# Microcontroller.net
KiCad netlist of a schematic drawn in Altium Designer
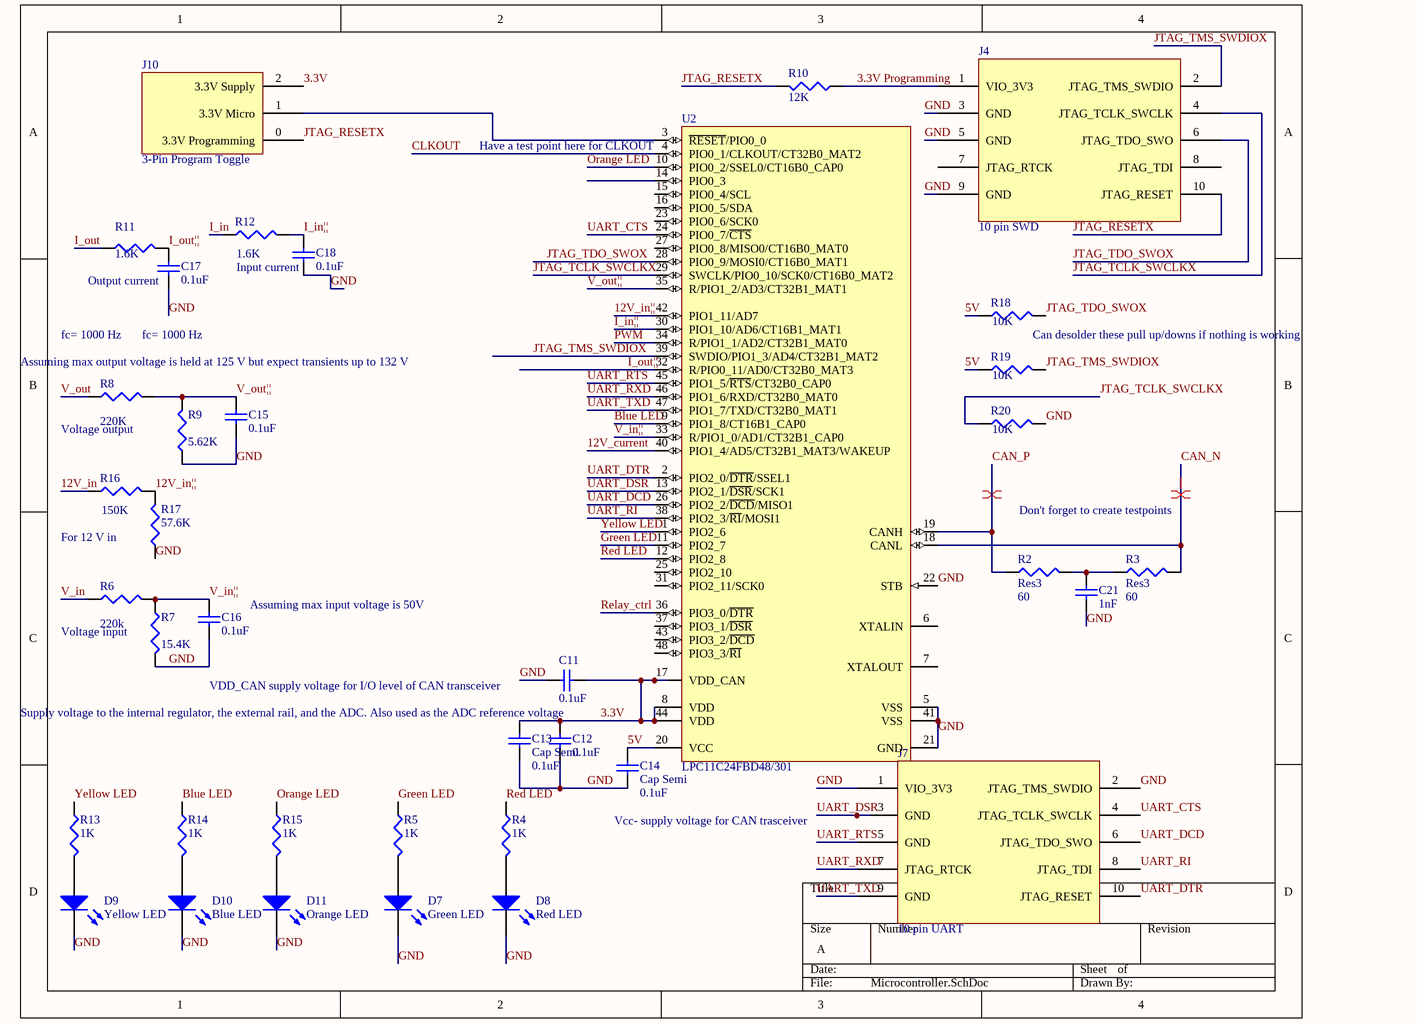
[diagram p0: Microcontroller.SchDoc]

(export (version "E")
  (design (tool "Eeschema 10.0.6"))
  (components
    (comp (ref "C11")
      (value "0.1uF")
      (footprint "C1206")
      (description "Capacitor (Semiconductor SIM Model)")
      (fields (field (name "Comment") "Cap Semi") (field (name "PUBLISHER") "Altium Limited"))
      (libsource (lib "Miscellaneous Devices") (part "Cap Semi"))
    )
    (comp (ref "C12")
      (value "0.1uF")
      (footprint "C1206")
      (description "Capacitor (Semiconductor SIM Model)")
      (fields (field (name "Comment") "Cap Semi") (field (name "PUBLISHER") "Altium Limited"))
      (libsource (lib "Miscellaneous Devices") (part "Cap Semi"))
    )
    (comp (ref "C13")
      (value "Cap Semi")
      (footprint "C1206")
      (description "Capacitor (Semiconductor SIM Model)")
      (fields (field (name "ALTIUM_VALUE") "0.1uF") (field (name "PUBLISHER") "Altium Limited"))
      (libsource (lib "Miscellaneous Devices") (part "Cap Semi"))
    )
    (comp (ref "C14")
      (value "Cap Semi")
      (footprint "C1206")
      (description "Capacitor (Semiconductor SIM Model)")
      (fields (field (name "ALTIUM_VALUE") "0.1uF") (field (name "PUBLISHER") "Altium Limited"))
      (libsource (lib "Miscellaneous Devices") (part "Cap Semi"))
    )
    (comp (ref "C15")
      (value "0.1uF")
      (footprint "C1206")
      (description "Capacitor (Semiconductor SIM Model)")
      (fields (field (name "Comment") "Cap Semi") (field (name "PUBLISHER") "Altium Limited"))
      (libsource (lib "Miscellaneous Devices") (part "Cap Semi"))
    )
    (comp (ref "C16")
      (value "0.1uF")
      (footprint "C1206")
      (description "Capacitor (Semiconductor SIM Model)")
      (fields (field (name "Comment") "Cap Semi") (field (name "PUBLISHER") "Altium Limited"))
      (libsource (lib "Miscellaneous Devices") (part "Cap Semi"))
    )
    (comp (ref "C17")
      (value "0.1uF")
      (footprint "C1206")
      (description "Capacitor (Semiconductor SIM Model)")
      (fields (field (name "Comment") "Cap Semi") (field (name "PUBLISHER") "Altium Limited"))
      (libsource (lib "Miscellaneous Devices") (part "Cap Semi"))
    )
    (comp (ref "C18")
      (value "0.1uF")
      (footprint "C1206")
      (description "Capacitor (Semiconductor SIM Model)")
      (fields (field (name "Comment") "Cap Semi") (field (name "PUBLISHER") "Altium Limited"))
      (libsource (lib "Miscellaneous Devices") (part "Cap Semi"))
    )
    (comp (ref "C21")
      (value "1nF")
      (footprint "C1206")
      (description "Capacitor (Semiconductor SIM Model)")
      (fields (field (name "Comment") "Cap Semi") (field (name "PUBLISHER") "Altium Limited"))
      (libsource (lib "Miscellaneous Devices") (part "Cap Semi"))
    )
    (comp (ref "D7")
      (value "Green LED")
      (footprint "C1206")
      (description "Typical INFRARED GaAs LED")
      (fields (field (name "PUBLISHER") "Altium Limited"))
      (libsource (lib "Miscellaneous Devices") (part "LED0"))
    )
    (comp (ref "D8")
      (value "Red LED")
      (footprint "C1206")
      (description "Typical INFRARED GaAs LED")
      (fields (field (name "PUBLISHER") "Altium Limited"))
      (libsource (lib "Miscellaneous Devices") (part "LED0"))
    )
    (comp (ref "D9")
      (value "Yellow LED")
      (footprint "C1206")
      (description "Typical INFRARED GaAs LED")
      (fields (field (name "PUBLISHER") "Altium Limited"))
      (libsource (lib "Miscellaneous Devices") (part "LED0"))
    )
    (comp (ref "D10")
      (value "Blue LED")
      (footprint "C1206")
      (description "Typical INFRARED GaAs LED")
      (fields (field (name "PUBLISHER") "Altium Limited"))
      (libsource (lib "Miscellaneous Devices") (part "LED0"))
    )
    (comp (ref "D11")
      (value "Orange LED")
      (footprint "C1206")
      (description "Typical INFRARED GaAs LED")
      (fields (field (name "PUBLISHER") "Altium Limited"))
      (libsource (lib "Miscellaneous Devices") (part "LED0"))
    )
    (comp (ref "J4")
      (value "10 pin SWD")
      (footprint "10 Pin JTAG/SWD")
      (libsource (lib "Helianthus 2 Schematics") (part "10 pin JTAG"))
    )
    (comp (ref "J7")
      (value "10 pin UART")
      (footprint "10 Pin JTAG/SWD")
      (libsource (lib "Helianthus 2 Schematics") (part "10 pin JTAG"))
    )
    (comp (ref "J10")
      (value "3-Pin Program Toggle")
      (footprint "3-Pin Program Toggle")
      (libsource (lib "Helianthus 2 Schematics") (part "3-Pin Program Toggle"))
    )
    (comp (ref "R2")
      (value "Res3")
      (footprint "12Z-2010")
      (description "Resistor")
      (fields (field (name "ALTIUM_VALUE") "60") (field (name "PUBLISHER") "Altium Limited"))
      (libsource (lib "Miscellaneous Devices") (part "Res3"))
    )
    (comp (ref "R3")
      (value "Res3")
      (footprint "12Z-2010")
      (description "Resistor")
      (fields (field (name "ALTIUM_VALUE") "60") (field (name "PUBLISHER") "Altium Limited"))
      (libsource (lib "Miscellaneous Devices") (part "Res3"))
    )
    (comp (ref "R4")
      (value "1K")
      (footprint "C1206")
      (description "Resistor")
      (fields (field (name "Comment") "Res3") (field (name "PUBLISHER") "Altium Limited"))
      (libsource (lib "Miscellaneous Devices") (part "Res3"))
    )
    (comp (ref "R5")
      (value "1K")
      (footprint "C1206")
      (description "Resistor")
      (fields (field (name "Comment") "Res3") (field (name "PUBLISHER") "Altium Limited"))
      (libsource (lib "Miscellaneous Devices") (part "Res3"))
    )
    (comp (ref "R6")
      (value "220k")
      (footprint "C1206")
      (description "Resistor")
      (fields (field (name "Comment") "Res3") (field (name "PUBLISHER") "Altium Limited"))
      (libsource (lib "Miscellaneous Devices") (part "Res3"))
    )
    (comp (ref "R7")
      (value "15.4K")
      (footprint "C1206")
      (description "Resistor")
      (fields (field (name "Comment") "Res3") (field (name "PUBLISHER") "Altium Limited"))
      (libsource (lib "Miscellaneous Devices") (part "Res3"))
    )
    (comp (ref "R8")
      (value "220K")
      (footprint "C1206")
      (description "Resistor")
      (fields (field (name "Comment") "Res3") (field (name "PUBLISHER") "Altium Limited"))
      (libsource (lib "Miscellaneous Devices") (part "Res3"))
    )
    (comp (ref "R9")
      (value "5.62K")
      (footprint "C1206")
      (description "Resistor")
      (fields (field (name "Comment") "Res3") (field (name "PUBLISHER") "Altium Limited"))
      (libsource (lib "Miscellaneous Devices") (part "Res3"))
    )
    (comp (ref "R10")
      (value "12K")
      (footprint "C1206")
      (description "Resistor")
      (fields (field (name "Comment") "Res3") (field (name "PUBLISHER") "Altium Limited"))
      (libsource (lib "Miscellaneous Devices") (part "Res3"))
    )
    (comp (ref "R11")
      (value "1.6K")
      (footprint "C1206")
      (description "Resistor")
      (fields (field (name "Comment") "Res3") (field (name "PUBLISHER") "Altium Limited"))
      (libsource (lib "Miscellaneous Devices") (part "Res3"))
    )
    (comp (ref "R12")
      (value "1.6K")
      (footprint "C1206")
      (description "Resistor")
      (fields (field (name "Comment") "Res3") (field (name "PUBLISHER") "Altium Limited"))
      (libsource (lib "Miscellaneous Devices") (part "Res3"))
    )
    (comp (ref "R13")
      (value "1K")
      (footprint "C1206")
      (description "Resistor")
      (fields (field (name "Comment") "Res3") (field (name "PUBLISHER") "Altium Limited"))
      (libsource (lib "Miscellaneous Devices") (part "Res3"))
    )
    (comp (ref "R14")
      (value "1K")
      (footprint "C1206")
      (description "Resistor")
      (fields (field (name "Comment") "Res3") (field (name "PUBLISHER") "Altium Limited"))
      (libsource (lib "Miscellaneous Devices") (part "Res3"))
    )
    (comp (ref "R15")
      (value "1K")
      (footprint "C1206")
      (description "Resistor")
      (fields (field (name "Comment") "Res3") (field (name "PUBLISHER") "Altium Limited"))
      (libsource (lib "Miscellaneous Devices") (part "Res3"))
    )
    (comp (ref "R16")
      (value "150K")
      (footprint "C1206")
      (description "Resistor")
      (fields (field (name "Comment") "Res3") (field (name "PUBLISHER") "Altium Limited"))
      (libsource (lib "Miscellaneous Devices") (part "Res3"))
    )
    (comp (ref "R17")
      (value "57.6K")
      (footprint "C1206")
      (description "Resistor")
      (fields (field (name "Comment") "Res3") (field (name "PUBLISHER") "Altium Limited"))
      (libsource (lib "Miscellaneous Devices") (part "Res3"))
    )
    (comp (ref "R18")
      (value "10K")
      (footprint "C1206")
      (description "Resistor")
      (fields (field (name "Comment") "Res3") (field (name "PUBLISHER") "Altium Limited"))
      (libsource (lib "Miscellaneous Devices") (part "Res3"))
    )
    (comp (ref "R19")
      (value "10K")
      (footprint "C1206")
      (description "Resistor")
      (fields (field (name "Comment") "Res3") (field (name "PUBLISHER") "Altium Limited"))
      (libsource (lib "Miscellaneous Devices") (part "Res3"))
    )
    (comp (ref "R20")
      (value "10K")
      (footprint "C1206")
      (description "Resistor")
      (fields (field (name "Comment") "Res3") (field (name "PUBLISHER") "Altium Limited"))
      (libsource (lib "Miscellaneous Devices") (part "Res3"))
    )
    (comp (ref "U2")
      (value "LPC11C24FBD48/301")
      (footprint "SOT313-2_V")
      (libsource (lib "NXP Semiconductors Cortex-M0") (part "LPC11C24FBD48/301"))
    )
  )
  (nets
    (net (code "1") (name "/3.3V") (class "Default")
      (node (ref "C11") (pin "1") (pinfunction "1_1") (pintype "passive"))
      (node (ref "C12") (pin "2") (pinfunction "2_2") (pintype "passive"))
      (node (ref "C13") (pin "2") (pinfunction "2_2") (pintype "passive"))
      (node (ref "J10") (pin "2") (pinfunction "3.3V_Supply_2") (pintype "passive"))
      (node (ref "U2") (pin "17") (pinfunction "VDD_CAN_17") (pintype "power_in"))
      (node (ref "U2") (pin "44") (pinfunction "VDD_44") (pintype "power_in"))
      (node (ref "U2") (pin "8") (pinfunction "VDD_8") (pintype "power_in"))
    )
    (net (code "2") (name "/3.3V Programming") (class "Default")
      (node (ref "J4") (pin "1") (pinfunction "VIO_3V3_1") (pintype "passive"))
      (node (ref "R10") (pin "1") (pinfunction "1_1") (pintype "passive"))
    )
    (net (code "3") (name "/5V") (class "Default")
      (node (ref "C14") (pin "2") (pinfunction "2_2") (pintype "passive"))
      (node (ref "R18") (pin "1") (pinfunction "1_1") (pintype "passive"))
      (node (ref "R19") (pin "1") (pinfunction "1_1") (pintype "passive"))
      (node (ref "U2") (pin "20") (pinfunction "VCC_20") (pintype "power_in"))
    )
    (net (code "4") (name "/12V_current") (class "Default")
      (node (ref "U2") (pin "40") (pinfunction "PIO1_4/AD5/CT32B1_MAT3/WAKEUP_40") (pintype "bidirectional"))
    )
    (net (code "5") (name "/12V_in") (class "Default")
      (node (ref "R16") (pin "1") (pinfunction "1_1") (pintype "passive"))
    )
    (net (code "6") (name "/12V_inΖ") (class "Default")
      (node (ref "R16") (pin "2") (pinfunction "2_2") (pintype "passive"))
      (node (ref "R17") (pin "2") (pinfunction "2_2") (pintype "passive"))
      (node (ref "U2") (pin "42") (pinfunction "PIO1_11/AD7_42") (pintype "bidirectional"))
    )
    (net (code "7") (name "/Blue LED") (class "Default")
      (node (ref "R14") (pin "1") (pinfunction "1_1") (pintype "passive"))
      (node (ref "U2") (pin "9") (pinfunction "PIO1_8/CT16B1_CAP0_9") (pintype "bidirectional"))
    )
    (net (code "8") (name "/CAN_N") (class "Default")
      (node (ref "R3") (pin "2") (pinfunction "2_2") (pintype "passive"))
      (node (ref "U2") (pin "18") (pinfunction "CANL_18") (pintype "bidirectional"))
    )
    (net (code "9") (name "/CAN_P") (class "Default")
      (node (ref "R2") (pin "1") (pinfunction "1_1") (pintype "passive"))
      (node (ref "U2") (pin "19") (pinfunction "CANH_19") (pintype "bidirectional"))
    )
    (net (code "10") (name "/CLKOUT") (class "Default")
      (node (ref "U2") (pin "4") (pinfunction "PIO0_1/CLKOUT/CT32B0_MAT2_4") (pintype "bidirectional"))
    )
    (net (code "11") (name "/GND") (class "Default")
      (node (ref "C11") (pin "2") (pinfunction "2_2") (pintype "passive"))
      (node (ref "C12") (pin "1") (pinfunction "1_1") (pintype "passive"))
      (node (ref "C13") (pin "1") (pinfunction "1_1") (pintype "passive"))
      (node (ref "C14") (pin "1") (pinfunction "1_1") (pintype "passive"))
      (node (ref "C15") (pin "1") (pinfunction "1_1") (pintype "passive"))
      (node (ref "C16") (pin "2") (pinfunction "2_2") (pintype "passive"))
      (node (ref "C17") (pin "2") (pinfunction "2_2") (pintype "passive"))
      (node (ref "C18") (pin "2") (pinfunction "2_2") (pintype "passive"))
      (node (ref "C21") (pin "2") (pinfunction "2_2") (pintype "passive"))
      (node (ref "D10") (pin "2") (pinfunction "K_2") (pintype "passive"))
      (node (ref "D11") (pin "2") (pinfunction "K_2") (pintype "passive"))
      (node (ref "D7") (pin "2") (pinfunction "K_2") (pintype "passive"))
      (node (ref "D8") (pin "2") (pinfunction "K_2") (pintype "passive"))
      (node (ref "D9") (pin "2") (pinfunction "K_2") (pintype "passive"))
      (node (ref "J4") (pin "3") (pinfunction "GND_3") (pintype "passive"))
      (node (ref "J4") (pin "5") (pinfunction "GND_5") (pintype "passive"))
      (node (ref "J4") (pin "9") (pinfunction "GND_9") (pintype "passive"))
      (node (ref "J7") (pin "1") (pinfunction "VIO_3V3_1") (pintype "passive"))
      (node (ref "J7") (pin "2") (pinfunction "JTAG_TMS_SWDIO_2") (pintype "passive"))
      (node (ref "R17") (pin "1") (pinfunction "1_1") (pintype "passive"))
      (node (ref "R20") (pin "2") (pinfunction "2_2") (pintype "passive"))
      (node (ref "R7") (pin "2") (pinfunction "2_2") (pintype "passive"))
      (node (ref "R9") (pin "1") (pinfunction "1_1") (pintype "passive"))
      (node (ref "U2") (pin "21") (pinfunction "GND_21") (pintype "power_in"))
      (node (ref "U2") (pin "22") (pinfunction "STB_22") (pintype "input"))
      (node (ref "U2") (pin "41") (pinfunction "VSS_41") (pintype "power_in"))
      (node (ref "U2") (pin "5") (pinfunction "VSS_5") (pintype "power_in"))
    )
    (net (code "12") (name "/Green LED") (class "Default")
      (node (ref "R5") (pin "1") (pinfunction "1_1") (pintype "passive"))
      (node (ref "U2") (pin "11") (pinfunction "PIO2_7_11") (pintype "bidirectional"))
    )
    (net (code "13") (name "/I_in") (class "Default")
      (node (ref "R12") (pin "1") (pinfunction "1_1") (pintype "passive"))
    )
    (net (code "14") (name "/I_inΖ") (class "Default")
      (node (ref "C18") (pin "1") (pinfunction "1_1") (pintype "passive"))
      (node (ref "R12") (pin "2") (pinfunction "2_2") (pintype "passive"))
      (node (ref "U2") (pin "30") (pinfunction "PIO1_10/AD6/CT16B1_MAT1_30") (pintype "bidirectional"))
    )
    (net (code "15") (name "/I_out") (class "Default")
      (node (ref "R11") (pin "1") (pinfunction "1_1") (pintype "passive"))
    )
    (net (code "16") (name "/I_outΖ") (class "Default")
      (node (ref "C17") (pin "1") (pinfunction "1_1") (pintype "passive"))
      (node (ref "R11") (pin "2") (pinfunction "2_2") (pintype "passive"))
      (node (ref "U2") (pin "32") (pinfunction "R/PIO0_11/AD0/CT32B0_MAT3_32") (pintype "bidirectional"))
    )
    (net (code "17") (name "/JTAG_RESETX") (class "Default")
      (node (ref "J10") (pin "0") (pinfunction "3.3V_Programming_0") (pintype "passive"))
      (node (ref "J4") (pin "10") (pinfunction "JTAG_RESET_10") (pintype "passive"))
      (node (ref "R10") (pin "2") (pinfunction "2_2") (pintype "passive"))
    )
    (net (code "18") (name "/JTAG_TCLK_SWCLKX") (class "Default")
      (node (ref "J4") (pin "4") (pinfunction "JTAG_TCLK_SWCLK_4") (pintype "passive"))
      (node (ref "R20") (pin "1") (pinfunction "1_1") (pintype "passive"))
      (node (ref "U2") (pin "29") (pinfunction "SWCLK/PIO0_10/SCK0/CT16B0_MAT2_29") (pintype "bidirectional"))
    )
    (net (code "19") (name "/JTAG_TDO_SWOX") (class "Default")
      (node (ref "J4") (pin "6") (pinfunction "JTAG_TDO_SWO_6") (pintype "passive"))
      (node (ref "R18") (pin "2") (pinfunction "2_2") (pintype "passive"))
      (node (ref "U2") (pin "28") (pinfunction "PIO0_9/MOSI0/CT16B0_MAT1_28") (pintype "bidirectional"))
    )
    (net (code "20") (name "/JTAG_TMS_SWDIOX") (class "Default")
      (node (ref "J4") (pin "2") (pinfunction "JTAG_TMS_SWDIO_2") (pintype "passive"))
      (node (ref "R19") (pin "2") (pinfunction "2_2") (pintype "passive"))
      (node (ref "U2") (pin "39") (pinfunction "SWDIO/PIO1_3/AD4/CT32B1_MAT2_39") (pintype "bidirectional"))
    )
    (net (code "21") (name "/Orange LED") (class "Default")
      (node (ref "R15") (pin "1") (pinfunction "1_1") (pintype "passive"))
      (node (ref "U2") (pin "10") (pinfunction "PIO0_2/SSEL0/CT16B0_CAP0_10") (pintype "bidirectional"))
    )
    (net (code "22") (name "/PWM") (class "Default")
      (node (ref "U2") (pin "34") (pinfunction "R/PIO1_1/AD2/CT32B1_MAT0_34") (pintype "bidirectional"))
    )
    (net (code "23") (name "/Red LED") (class "Default")
      (node (ref "R4") (pin "1") (pinfunction "1_1") (pintype "passive"))
      (node (ref "U2") (pin "12") (pinfunction "PIO2_8_12") (pintype "bidirectional"))
    )
    (net (code "24") (name "/Relay_ctrl") (class "Default")
      (node (ref "U2") (pin "36") (pinfunction "PIO3_0/~{DTR}_36") (pintype "bidirectional"))
    )
    (net (code "25") (name "/UART_CTS") (class "Default")
      (node (ref "J7") (pin "4") (pinfunction "JTAG_TCLK_SWCLK_4") (pintype "passive"))
      (node (ref "U2") (pin "24") (pinfunction "PIO0_7/~{CTS}_24") (pintype "bidirectional"))
    )
    (net (code "26") (name "/UART_DCD") (class "Default")
      (node (ref "J7") (pin "6") (pinfunction "JTAG_TDO_SWO_6") (pintype "passive"))
      (node (ref "U2") (pin "26") (pinfunction "PIO2_2/~{DCD}/MISO1_26") (pintype "bidirectional"))
    )
    (net (code "27") (name "/UART_DSR") (class "Default")
      (node (ref "J7") (pin "3") (pinfunction "GND_3") (pintype "passive"))
      (node (ref "U2") (pin "13") (pinfunction "PIO2_1/~{DSR}/SCK1_13") (pintype "bidirectional"))
    )
    (net (code "28") (name "/UART_DTR") (class "Default")
      (node (ref "J7") (pin "10") (pinfunction "JTAG_RESET_10") (pintype "passive"))
      (node (ref "U2") (pin "2") (pinfunction "PIO2_0/~{DTR}/SSEL1_2") (pintype "bidirectional"))
    )
    (net (code "29") (name "/UART_RI") (class "Default")
      (node (ref "J7") (pin "8") (pinfunction "JTAG_TDI_8") (pintype "passive"))
      (node (ref "U2") (pin "38") (pinfunction "PIO2_3/~{RI}/MOSI1_38") (pintype "bidirectional"))
    )
    (net (code "30") (name "/UART_RTS") (class "Default")
      (node (ref "J7") (pin "5") (pinfunction "GND_5") (pintype "passive"))
      (node (ref "U2") (pin "45") (pinfunction "PIO1_5/~{RTS}/CT32B0_CAP0_45") (pintype "bidirectional"))
    )
    (net (code "31") (name "/UART_RXD") (class "Default")
      (node (ref "J7") (pin "7") (pinfunction "JTAG_RTCK_7") (pintype "passive"))
      (node (ref "U2") (pin "46") (pinfunction "PIO1_6/RXD/CT32B0_MAT0_46") (pintype "bidirectional"))
    )
    (net (code "32") (name "/UART_TXD") (class "Default")
      (node (ref "J7") (pin "9") (pinfunction "GND_9") (pintype "passive"))
      (node (ref "U2") (pin "47") (pinfunction "PIO1_7/TXD/CT32B0_MAT1_47") (pintype "bidirectional"))
    )
    (net (code "33") (name "/V_in") (class "Default")
      (node (ref "R6") (pin "1") (pinfunction "1_1") (pintype "passive"))
    )
    (net (code "34") (name "/V_inΖ") (class "Default")
      (node (ref "C16") (pin "1") (pinfunction "1_1") (pintype "passive"))
      (node (ref "R6") (pin "2") (pinfunction "2_2") (pintype "passive"))
      (node (ref "R7") (pin "1") (pinfunction "1_1") (pintype "passive"))
      (node (ref "U2") (pin "33") (pinfunction "R/PIO1_0/AD1/CT32B1_CAP0_33") (pintype "bidirectional"))
    )
    (net (code "35") (name "/V_out") (class "Default")
      (node (ref "R8") (pin "1") (pinfunction "1_1") (pintype "passive"))
    )
    (net (code "36") (name "/V_outΖ") (class "Default")
      (node (ref "C15") (pin "2") (pinfunction "2_2") (pintype "passive"))
      (node (ref "R8") (pin "2") (pinfunction "2_2") (pintype "passive"))
      (node (ref "R9") (pin "2") (pinfunction "2_2") (pintype "passive"))
      (node (ref "U2") (pin "35") (pinfunction "R/PIO1_2/AD3/CT32B1_MAT1_35") (pintype "bidirectional"))
    )
    (net (code "37") (name "/Yellow LED") (class "Default")
      (node (ref "R13") (pin "1") (pinfunction "1_1") (pintype "passive"))
      (node (ref "U2") (pin "1") (pinfunction "PIO2_6_1") (pintype "bidirectional"))
    )
    (net (code "38") (name "Net-(C21-Pad1)") (class "Default")
      (node (ref "C21") (pin "1") (pinfunction "1_1") (pintype "passive"))
      (node (ref "R2") (pin "2") (pinfunction "2_2") (pintype "passive"))
      (node (ref "R3") (pin "1") (pinfunction "1_1") (pintype "passive"))
    )
    (net (code "39") (name "Net-(D7-A)") (class "Default")
      (node (ref "D7") (pin "1") (pinfunction "A_1") (pintype "passive"))
      (node (ref "R5") (pin "2") (pinfunction "2_2") (pintype "passive"))
    )
    (net (code "40") (name "Net-(D8-A)") (class "Default")
      (node (ref "D8") (pin "1") (pinfunction "A_1") (pintype "passive"))
      (node (ref "R4") (pin "2") (pinfunction "2_2") (pintype "passive"))
    )
    (net (code "41") (name "Net-(D9-A)") (class "Default")
      (node (ref "D9") (pin "1") (pinfunction "A_1") (pintype "passive"))
      (node (ref "R13") (pin "2") (pinfunction "2_2") (pintype "passive"))
    )
    (net (code "42") (name "Net-(D10-A)") (class "Default")
      (node (ref "D10") (pin "1") (pinfunction "A_1") (pintype "passive"))
      (node (ref "R14") (pin "2") (pinfunction "2_2") (pintype "passive"))
    )
    (net (code "43") (name "Net-(D11-A)") (class "Default")
      (node (ref "D11") (pin "1") (pinfunction "A_1") (pintype "passive"))
      (node (ref "R15") (pin "2") (pinfunction "2_2") (pintype "passive"))
    )
    (net (code "44") (name "Net-(J10-3.3V_Micro)") (class "Default")
      (node (ref "J10") (pin "1") (pinfunction "3.3V_Micro_1") (pintype "passive"))
      (node (ref "U2") (pin "3") (pinfunction "~{RESET}/PIO0_0_3") (pintype "bidirectional"))
    )
    (net (code "45") (name "unconnected-(J4-JTAG_RTCK-Pad7)") (class "Default")
      (node (ref "J4") (pin "7") (pinfunction "JTAG_RTCK_7") (pintype "passive"))
    )
    (net (code "46") (name "unconnected-(J4-JTAG_TDI-Pad8)") (class "Default")
      (node (ref "J4") (pin "8") (pinfunction "JTAG_TDI_8") (pintype "passive"))
    )
    (net (code "47") (name "unconnected-(U2-PIO0_3-Pad14)") (class "Default")
      (node (ref "U2") (pin "14") (pinfunction "PIO0_3_14") (pintype "bidirectional"))
    )
    (net (code "48") (name "unconnected-(U2-PIO0_4{slash}SCL-Pad15)") (class "Default")
      (node (ref "U2") (pin "15") (pinfunction "PIO0_4/SCL_15") (pintype "bidirectional"))
    )
    (net (code "49") (name "unconnected-(U2-PIO0_5{slash}SDA-Pad16)") (class "Default")
      (node (ref "U2") (pin "16") (pinfunction "PIO0_5/SDA_16") (pintype "bidirectional"))
    )
    (net (code "50") (name "unconnected-(U2-PIO0_6{slash}SCK0-Pad23)") (class "Default")
      (node (ref "U2") (pin "23") (pinfunction "PIO0_6/SCK0_23") (pintype "bidirectional"))
    )
    (net (code "51") (name "unconnected-(U2-PIO0_8{slash}MISO0{slash}CT16B0_MAT0-Pad27)") (class "Default")
      (node (ref "U2") (pin "27") (pinfunction "PIO0_8/MISO0/CT16B0_MAT0_27") (pintype "bidirectional"))
    )
    (net (code "52") (name "unconnected-(U2-PIO2_10-Pad25)") (class "Default")
      (node (ref "U2") (pin "25") (pinfunction "PIO2_10_25") (pintype "bidirectional"))
    )
    (net (code "53") (name "unconnected-(U2-PIO2_11{slash}SCK0-Pad31)") (class "Default")
      (node (ref "U2") (pin "31") (pinfunction "PIO2_11/SCK0_31") (pintype "bidirectional"))
    )
    (net (code "54") (name "unconnected-(U2-PIO3_1{slash}~{DSR}-Pad37)") (class "Default")
      (node (ref "U2") (pin "37") (pinfunction "PIO3_1/~{DSR}_37") (pintype "bidirectional"))
    )
    (net (code "55") (name "unconnected-(U2-PIO3_2{slash}~{DCD}-Pad43)") (class "Default")
      (node (ref "U2") (pin "43") (pinfunction "PIO3_2/~{DCD}_43") (pintype "bidirectional"))
    )
    (net (code "56") (name "unconnected-(U2-PIO3_3{slash}~{RI}-Pad48)") (class "Default")
      (node (ref "U2") (pin "48") (pinfunction "PIO3_3/~{RI}_48") (pintype "bidirectional"))
    )
    (net (code "57") (name "unconnected-(U2-XTALIN-Pad6)") (class "Default")
      (node (ref "U2") (pin "6") (pinfunction "XTALIN_6") (pintype "passive"))
    )
    (net (code "58") (name "unconnected-(U2-XTALOUT-Pad7)") (class "Default")
      (node (ref "U2") (pin "7") (pinfunction "XTALOUT_7") (pintype "passive"))
    )
  )
)
